# USBtinyISP.net
KiCad netlist of a schematic drawn in Altium Designer
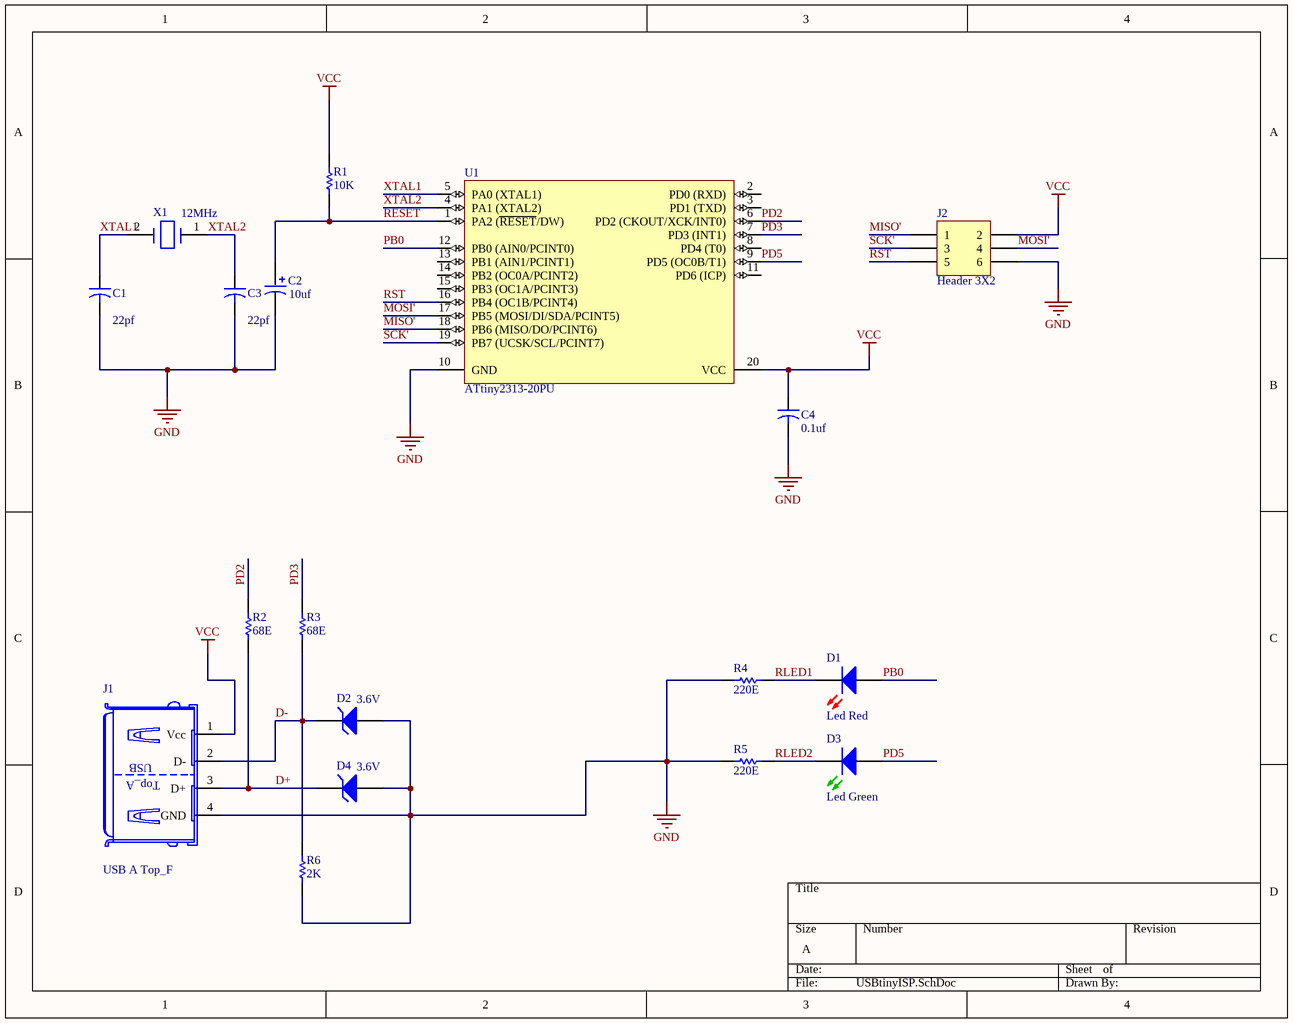
[diagram p0: USBtinyISP.SchDoc]

(export (version "E")
  (design (tool "Eeschema 10.0.6"))
  (components
    (comp (ref "C1")
      (value "22pf")
      (footprint "CAPR5-4X5")
      (description "Capacitor")
      (fields (field (name "Comment") "Cap2") (field (name "PUBLISHER") "Altium Limited"))
      (libsource (lib "Miscellaneous Devices") (part "Cap2"))
    )
    (comp (ref "C2")
      (value "10uf")
      (footprint "CAP-ELECTROLITE")
      (description "Capacitor Polar")
      (libsource (lib "Devindia_v4.0") (part "Cap- polarized"))
    )
    (comp (ref "C3")
      (value "22pf")
      (footprint "CAPR5-4X5")
      (description "Capacitor")
      (fields (field (name "Comment") "Cap2") (field (name "PUBLISHER") "Altium Limited"))
      (libsource (lib "Miscellaneous Devices") (part "Cap2"))
    )
    (comp (ref "C4")
      (value "0.1uf")
      (footprint "CAPR5-4X5")
      (description "Capacitor")
      (fields (field (name "Comment") "Cap2") (field (name "PUBLISHER") "Altium Limited"))
      (libsource (lib "Miscellaneous Devices") (part "Cap2"))
    )
    (comp (ref "D1")
      (value "Led Red")
      (footprint "LED-RED")
      (fields (field (name "PUBLISHER") "Altium Limited"))
      (libsource (lib "Devindia_v4.0") (part "Led Red"))
    )
    (comp (ref "D2")
      (value "3.6V")
      (footprint "D Zener")
      (description "Zenor Diode")
      (fields (field (name "PUBLISHER") "Altium Limited"))
      (libsource (lib "Devindia_v4.0") (part "Zenor Diode"))
    )
    (comp (ref "D3")
      (value "Led Green")
      (footprint "LED-GREEN")
      (fields (field (name "PUBLISHER") "Altium Limited"))
      (libsource (lib "Devindia_v4.0") (part "Led Green"))
    )
    (comp (ref "D4")
      (value "3.6V")
      (footprint "D Zener")
      (description "Zenor Diode")
      (fields (field (name "PUBLISHER") "Altium Limited"))
      (libsource (lib "Devindia_v4.0") (part "Zenor Diode"))
    )
    (comp (ref "J1")
      (value "USB A Top_F")
      (footprint "USB Type A")
      (libsource (lib "Devindia_v4.0") (part "USB A Top_F"))
    )
    (comp (ref "J2")
      (value "Header 3X2")
      (footprint "HDR2X3")
      (description "Header, 3-Pin, Dual row")
      (fields (field (name "PUBLISHER") "Altium Limited"))
      (libsource (lib "Miscellaneous Connectors") (part "Header 3X2"))
    )
    (comp (ref "R1")
      (value "10K")
      (footprint "AXIAL-0.3")
      (description "Resistor")
      (fields (field (name "Comment") "Res1") (field (name "PUBLISHER") "Altium Limited"))
      (libsource (lib "Miscellaneous Devices") (part "Res1"))
    )
    (comp (ref "R2")
      (value "68E")
      (footprint "AXIAL-0.3")
      (description "Resistor")
      (fields (field (name "Comment") "Res1") (field (name "PUBLISHER") "Altium Limited"))
      (libsource (lib "Miscellaneous Devices") (part "Res1"))
    )
    (comp (ref "R3")
      (value "68E")
      (footprint "AXIAL-0.3")
      (description "Resistor")
      (fields (field (name "Comment") "Res1") (field (name "PUBLISHER") "Altium Limited"))
      (libsource (lib "Miscellaneous Devices") (part "Res1"))
    )
    (comp (ref "R4")
      (value "220E")
      (footprint "AXIAL-0.3")
      (description "Resistor")
      (fields (field (name "Comment") "Res1") (field (name "PUBLISHER") "Altium Limited"))
      (libsource (lib "Miscellaneous Devices") (part "Res1"))
    )
    (comp (ref "R5")
      (value "220E")
      (footprint "AXIAL-0.3")
      (description "Resistor")
      (fields (field (name "Comment") "Res1") (field (name "PUBLISHER") "Altium Limited"))
      (libsource (lib "Miscellaneous Devices") (part "Res1"))
    )
    (comp (ref "R6")
      (value "2K")
      (footprint "AXIAL-0.3")
      (description "Resistor")
      (fields (field (name "Comment") "Res1") (field (name "PUBLISHER") "Altium Limited"))
      (libsource (lib "Miscellaneous Devices") (part "Res1"))
    )
    (comp (ref "U1")
      (value "ATtiny2313-20PU")
      (footprint "20P3")
      (fields (field (name "PUBLISHER") "Altium Limited"))
      (libsource (lib "Atmel Microcontroller 8-Bit tinyAVR") (part "ATtiny2313-20PU"))
    )
    (comp (ref "X1")
      (value "12MHz")
      (footprint "XTAL-SMALL")
      (description "Crystal Oscillator")
      (fields (field (name "Comment") "Crystal Small") (field (name "PUBLISHER") "Altium Limited"))
      (libsource (lib "Devindia_v4.0") (part "Crystal Small"))
    )
  )
  (nets
    (net (code "1") (name "/D+") (class "Default")
      (node (ref "D4") (pin "2") (pinfunction "K_2") (pintype "passive"))
      (node (ref "J1") (pin "3") (pinfunction "D+_3") (pintype "passive"))
      (node (ref "R2") (pin "1") (pinfunction "1_1") (pintype "passive"))
    )
    (net (code "2") (name "/D-") (class "Default")
      (node (ref "D2") (pin "2") (pinfunction "K_2") (pintype "passive"))
      (node (ref "J1") (pin "2") (pinfunction "D-_2") (pintype "passive"))
      (node (ref "R3") (pin "1") (pinfunction "1_1") (pintype "passive"))
      (node (ref "R6") (pin "2") (pinfunction "2_2") (pintype "passive"))
    )
    (net (code "3") (name "/MISO'") (class "Default")
      (node (ref "J2") (pin "1") (pinfunction "1_1") (pintype "passive"))
      (node (ref "U1") (pin "18") (pinfunction "PB6_(MISO/DO/PCINT6)_18") (pintype "bidirectional"))
    )
    (net (code "4") (name "/MOSI'") (class "Default")
      (node (ref "J2") (pin "4") (pinfunction "4_4") (pintype "passive"))
      (node (ref "U1") (pin "17") (pinfunction "PB5_(MOSI/DI/SDA/PCINT5)_17") (pintype "bidirectional"))
    )
    (net (code "5") (name "/PB0") (class "Default")
      (node (ref "D1") (pin "1") (pinfunction "A_1") (pintype "passive"))
      (node (ref "U1") (pin "12") (pinfunction "PB0_(AIN0/PCINT0)_12") (pintype "bidirectional"))
    )
    (net (code "6") (name "/PD2") (class "Default")
      (node (ref "R2") (pin "2") (pinfunction "2_2") (pintype "passive"))
      (node (ref "U1") (pin "6") (pinfunction "PD2_(CKOUT/XCK/INT0)_6") (pintype "bidirectional"))
    )
    (net (code "7") (name "/PD3") (class "Default")
      (node (ref "R3") (pin "2") (pinfunction "2_2") (pintype "passive"))
      (node (ref "U1") (pin "7") (pinfunction "PD3_(INT1)_7") (pintype "bidirectional"))
    )
    (net (code "8") (name "/PD5") (class "Default")
      (node (ref "D3") (pin "1") (pinfunction "A_1") (pintype "passive"))
      (node (ref "U1") (pin "9") (pinfunction "PD5_(OC0B/T1)_9") (pintype "bidirectional"))
    )
    (net (code "9") (name "/RESET") (class "Default")
      (node (ref "C2") (pin "1") (pinfunction "1_1") (pintype "passive"))
      (node (ref "R1") (pin "1") (pinfunction "1_1") (pintype "passive"))
      (node (ref "U1") (pin "1") (pinfunction "PA2_(~{RESET}/DW)_1") (pintype "bidirectional"))
    )
    (net (code "10") (name "/RLED1") (class "Default")
      (node (ref "D1") (pin "2") (pinfunction "K_2") (pintype "passive"))
      (node (ref "R4") (pin "2") (pinfunction "2_2") (pintype "passive"))
    )
    (net (code "11") (name "/RLED2") (class "Default")
      (node (ref "D3") (pin "2") (pinfunction "K_2") (pintype "passive"))
      (node (ref "R5") (pin "2") (pinfunction "2_2") (pintype "passive"))
    )
    (net (code "12") (name "/RST") (class "Default")
      (node (ref "J2") (pin "5") (pinfunction "5_5") (pintype "passive"))
      (node (ref "U1") (pin "16") (pinfunction "PB4_(OC1B/PCINT4)_16") (pintype "bidirectional"))
    )
    (net (code "13") (name "/SCK'") (class "Default")
      (node (ref "J2") (pin "3") (pinfunction "3_3") (pintype "passive"))
      (node (ref "U1") (pin "19") (pinfunction "PB7_(UCSK/SCL/PCINT7)_19") (pintype "bidirectional"))
    )
    (net (code "14") (name "/XTAL1") (class "Default")
      (node (ref "C1") (pin "1") (pinfunction "1_1") (pintype "passive"))
      (node (ref "U1") (pin "5") (pinfunction "PA0_(XTAL1)_5") (pintype "bidirectional"))
      (node (ref "X1") (pin "2") (pinfunction "OSC2_2") (pintype "passive"))
    )
    (net (code "15") (name "/XTAL2") (class "Default")
      (node (ref "C3") (pin "1") (pinfunction "1_1") (pintype "passive"))
      (node (ref "U1") (pin "4") (pinfunction "PA1_(XTAL2)_4") (pintype "bidirectional"))
      (node (ref "X1") (pin "1") (pinfunction "OSC1_1") (pintype "passive"))
    )
    (net (code "16") (name "GND") (class "Default")
      (node (ref "C1") (pin "2") (pinfunction "2_2") (pintype "passive"))
      (node (ref "C2") (pin "2") (pinfunction "2_2") (pintype "passive"))
      (node (ref "C3") (pin "2") (pinfunction "2_2") (pintype "passive"))
      (node (ref "C4") (pin "2") (pinfunction "2_2") (pintype "passive"))
      (node (ref "D2") (pin "1") (pinfunction "A_1") (pintype "passive"))
      (node (ref "D4") (pin "1") (pinfunction "A_1") (pintype "passive"))
      (node (ref "J1") (pin "4") (pinfunction "GND_4") (pintype "passive"))
      (node (ref "J2") (pin "6") (pinfunction "6_6") (pintype "passive"))
      (node (ref "R4") (pin "1") (pinfunction "1_1") (pintype "passive"))
      (node (ref "R5") (pin "1") (pinfunction "1_1") (pintype "passive"))
      (node (ref "R6") (pin "1") (pinfunction "1_1") (pintype "passive"))
      (node (ref "U1") (pin "10") (pinfunction "GND_10") (pintype "power_in"))
    )
    (net (code "17") (name "VCC") (class "Default")
      (node (ref "C4") (pin "1") (pinfunction "1_1") (pintype "passive"))
      (node (ref "J1") (pin "1") (pinfunction "Vcc_1") (pintype "passive"))
      (node (ref "J2") (pin "2") (pinfunction "2_2") (pintype "passive"))
      (node (ref "R1") (pin "2") (pinfunction "2_2") (pintype "passive"))
      (node (ref "U1") (pin "20") (pinfunction "VCC_20") (pintype "power_in"))
    )
    (net (code "18") (name "unconnected-(U1-PB1_(AIN1{slash}PCINT1)-Pad13)") (class "Default")
      (node (ref "U1") (pin "13") (pinfunction "PB1_(AIN1/PCINT1)_13") (pintype "bidirectional"))
    )
    (net (code "19") (name "unconnected-(U1-PB2_(OC0A{slash}PCINT2)-Pad14)") (class "Default")
      (node (ref "U1") (pin "14") (pinfunction "PB2_(OC0A/PCINT2)_14") (pintype "bidirectional"))
    )
    (net (code "20") (name "unconnected-(U1-PB3_(OC1A{slash}PCINT3)-Pad15)") (class "Default")
      (node (ref "U1") (pin "15") (pinfunction "PB3_(OC1A/PCINT3)_15") (pintype "bidirectional"))
    )
    (net (code "21") (name "unconnected-(U1-PD0_(RXD)-Pad2)") (class "Default")
      (node (ref "U1") (pin "2") (pinfunction "PD0_(RXD)_2") (pintype "bidirectional"))
    )
    (net (code "22") (name "unconnected-(U1-PD1_(TXD)-Pad3)") (class "Default")
      (node (ref "U1") (pin "3") (pinfunction "PD1_(TXD)_3") (pintype "bidirectional"))
    )
    (net (code "23") (name "unconnected-(U1-PD4_(T0)-Pad8)") (class "Default")
      (node (ref "U1") (pin "8") (pinfunction "PD4_(T0)_8") (pintype "bidirectional"))
    )
    (net (code "24") (name "unconnected-(U1-PD6_(ICP)-Pad11)") (class "Default")
      (node (ref "U1") (pin "11") (pinfunction "PD6_(ICP)_11") (pintype "bidirectional"))
    )
  )
)
